# main.net
KiCad netlist of a schematic drawn in Altium Designer
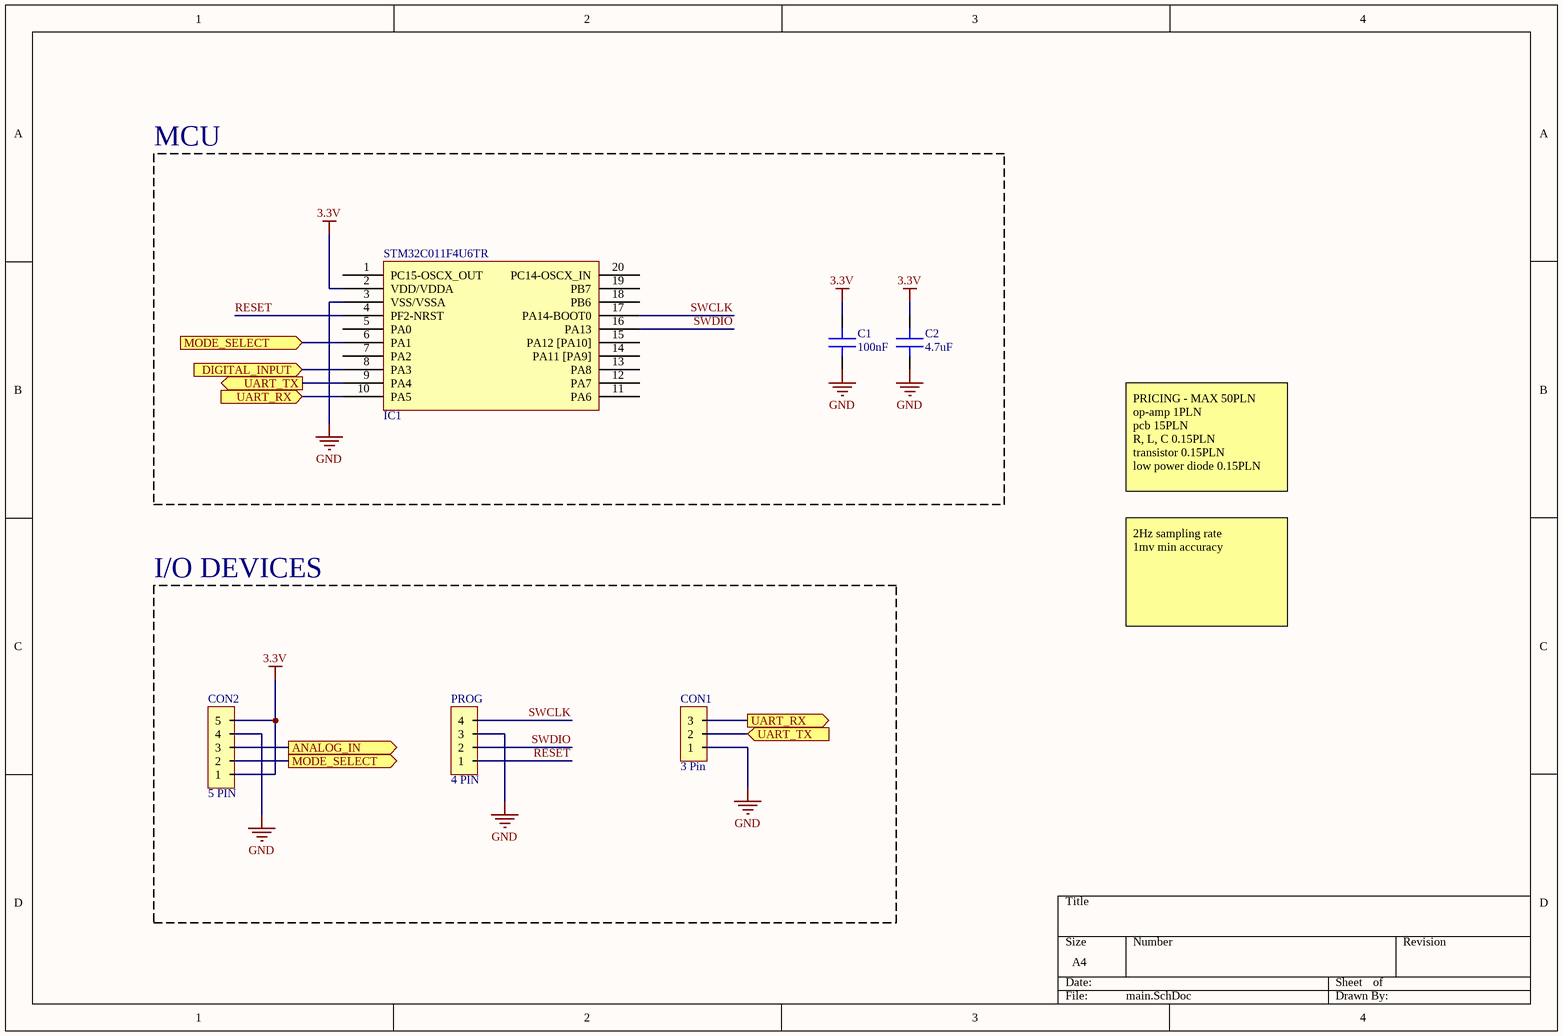
[diagram p0: main.SchDoc]

(export (version "E")
  (design (tool "Eeschema 10.0.6"))
  (components
    (comp (ref "C1")
      (value "100nF")
      (footprint "C 0603")
      (description "MLCC Capacitor")
      (libsource (lib "sigma-delta-adc-uart") (part "Capacitor"))
    )
    (comp (ref "C2")
      (value "4.7uF")
      (footprint "C 0603")
      (description "MLCC Capacitor")
      (libsource (lib "sigma-delta-adc-uart") (part "Capacitor"))
    )
    (comp (ref "CON1")
      (value "3 Pin")
      (footprint "Goldpin 2.54MM 3P")
      (libsource (lib "sigma-delta-adc-uart") (part "3 Pin"))
    )
    (comp (ref "CON2")
      (value "5 PIN")
      (footprint "Goldpin 2.54mm 5P")
      (libsource (lib "sigma-delta-adc-uart") (part "5 PIN"))
    )
    (comp (ref "IC1")
      (value "STM32C011F4U6TR")
      (footprint "UFQFPN20 - byMe")
      (libsource (lib "sigma-delta-adc-uart") (part "STM32C011F4U6TR"))
    )
    (comp (ref "PROG")
      (value "4 PIN")
      (footprint "BM04B-SRSS-TB")
      (libsource (lib "sigma-delta-adc-uart") (part "4 PIN"))
    )
  )
  (nets
    (net (code "1") (name "/ANALOG_IN") (class "Default")
      (node (ref "CON2") (pin "3") (pinfunction "3_3") (pintype "passive"))
    )
    (net (code "2") (name "/DIGITAL_INPUT") (class "Default")
      (node (ref "IC1") (pin "8") (pinfunction "PA3_8") (pintype "passive"))
    )
    (net (code "3") (name "/MODE_SELECT") (class "Default")
      (node (ref "CON2") (pin "2") (pinfunction "2_2") (pintype "passive"))
      (node (ref "IC1") (pin "6") (pinfunction "PA1_6") (pintype "passive"))
    )
    (net (code "4") (name "/RESET") (class "Default")
      (node (ref "IC1") (pin "4") (pinfunction "PF2-NRST_4") (pintype "passive"))
      (node (ref "PROG") (pin "1") (pinfunction "1_1") (pintype "passive"))
    )
    (net (code "5") (name "/SWCLK") (class "Default")
      (node (ref "IC1") (pin "17") (pinfunction "PA14-BOOT0_17") (pintype "passive"))
      (node (ref "PROG") (pin "4") (pinfunction "4_4") (pintype "passive"))
    )
    (net (code "6") (name "/SWDIO") (class "Default")
      (node (ref "IC1") (pin "16") (pinfunction "PA13_16") (pintype "passive"))
      (node (ref "PROG") (pin "2") (pinfunction "2_2") (pintype "passive"))
    )
    (net (code "7") (name "/UART_RX") (class "Default")
      (node (ref "CON1") (pin "3") (pinfunction "3_3") (pintype "passive"))
      (node (ref "IC1") (pin "10") (pinfunction "PA5_10") (pintype "passive"))
    )
    (net (code "8") (name "/UART_TX") (class "Default")
      (node (ref "CON1") (pin "2") (pinfunction "2_2") (pintype "passive"))
      (node (ref "IC1") (pin "9") (pinfunction "PA4_9") (pintype "passive"))
    )
    (net (code "9") (name "3.3V") (class "Default")
      (node (ref "C1") (pin "1") (pinfunction "1_1") (pintype "passive"))
      (node (ref "C2") (pin "1") (pinfunction "1_1") (pintype "passive"))
      (node (ref "CON2") (pin "1") (pinfunction "1_1") (pintype "passive"))
      (node (ref "CON2") (pin "5") (pinfunction "5_5") (pintype "passive"))
      (node (ref "IC1") (pin "2") (pinfunction "VDD/VDDA_2") (pintype "passive"))
    )
    (net (code "10") (name "GND") (class "Default")
      (node (ref "C1") (pin "2") (pinfunction "2_2") (pintype "passive"))
      (node (ref "C2") (pin "2") (pinfunction "2_2") (pintype "passive"))
      (node (ref "CON1") (pin "1") (pinfunction "1_1") (pintype "passive"))
      (node (ref "CON2") (pin "4") (pinfunction "4_4") (pintype "passive"))
      (node (ref "IC1") (pin "3") (pinfunction "VSS/VSSA_3") (pintype "passive"))
      (node (ref "PROG") (pin "3") (pinfunction "3_3") (pintype "passive"))
    )
    (net (code "11") (name "unconnected-(IC1-PA0-Pad5)") (class "Default")
      (node (ref "IC1") (pin "5") (pinfunction "PA0_5") (pintype "passive"))
    )
    (net (code "12") (name "unconnected-(IC1-PA2-Pad7)") (class "Default")
      (node (ref "IC1") (pin "7") (pinfunction "PA2_7") (pintype "passive"))
    )
    (net (code "13") (name "unconnected-(IC1-PA6-Pad11)") (class "Default")
      (node (ref "IC1") (pin "11") (pinfunction "PA6_11") (pintype "passive"))
    )
    (net (code "14") (name "unconnected-(IC1-PA7-Pad12)") (class "Default")
      (node (ref "IC1") (pin "12") (pinfunction "PA7_12") (pintype "passive"))
    )
    (net (code "15") (name "unconnected-(IC1-PA8-Pad13)") (class "Default")
      (node (ref "IC1") (pin "13") (pinfunction "PA8_13") (pintype "passive"))
    )
    (net (code "16") (name "unconnected-(IC1-PA11_[PA9]-Pad14)") (class "Default")
      (node (ref "IC1") (pin "14") (pinfunction "PA11_[PA9]_14") (pintype "passive"))
    )
    (net (code "17") (name "unconnected-(IC1-PA12_[PA10]-Pad15)") (class "Default")
      (node (ref "IC1") (pin "15") (pinfunction "PA12_[PA10]_15") (pintype "passive"))
    )
    (net (code "18") (name "unconnected-(IC1-PB6-Pad18)") (class "Default")
      (node (ref "IC1") (pin "18") (pinfunction "PB6_18") (pintype "passive"))
    )
    (net (code "19") (name "unconnected-(IC1-PB7-Pad19)") (class "Default")
      (node (ref "IC1") (pin "19") (pinfunction "PB7_19") (pintype "passive"))
    )
    (net (code "20") (name "unconnected-(IC1-PC14-OSCX_IN-Pad20)") (class "Default")
      (node (ref "IC1") (pin "20") (pinfunction "PC14-OSCX_IN_20") (pintype "passive"))
    )
    (net (code "21") (name "unconnected-(IC1-PC15-OSCX_OUT-Pad1)") (class "Default")
      (node (ref "IC1") (pin "1") (pinfunction "PC15-OSCX_OUT_1") (pintype "passive"))
    )
  )
)
